# CAN.net
KiCad netlist of a schematic drawn in Altium Designer
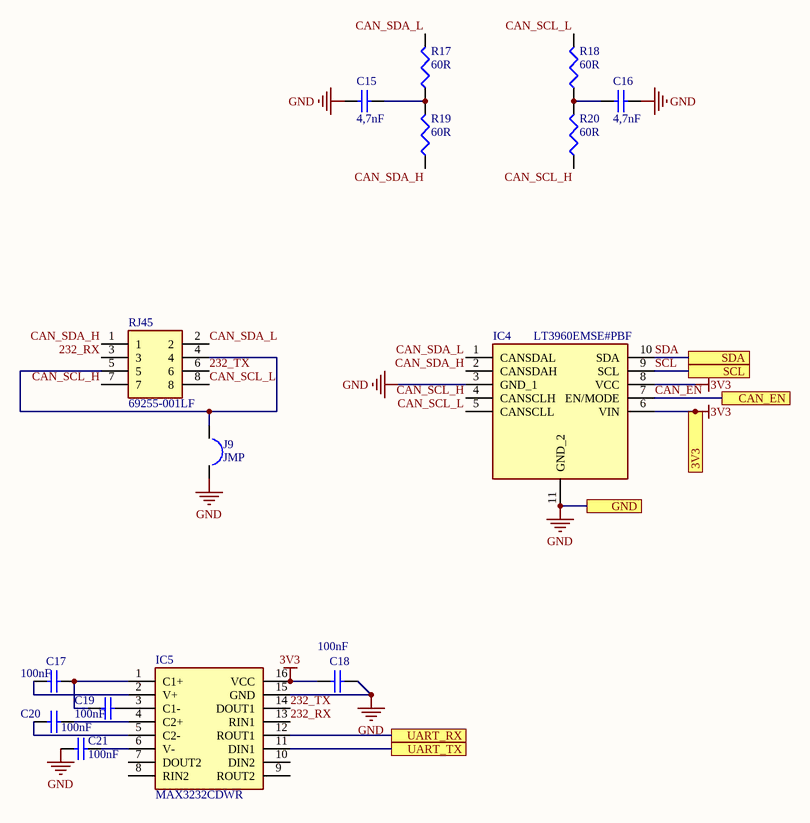
[diagram p0: CAN.SchDoc]

(export (version "E")
  (design (tool "Eeschema 10.0.6"))
  (components
    (comp (ref "C15")
      (value "4,7nF")
      (footprint "1608[0603]")
      (description "Capacitor (Semiconductor SIM Model)")
      (fields (field (name "PUBLISHER") "Altium Limited"))
      (libsource (lib "Miscellaneous Devices") (part "Cap Semi"))
    )
    (comp (ref "C16")
      (value "4,7nF")
      (footprint "1608[0603]")
      (description "Capacitor (Semiconductor SIM Model)")
      (fields (field (name "PUBLISHER") "Altium Limited"))
      (libsource (lib "Miscellaneous Devices") (part "Cap Semi"))
    )
    (comp (ref "C17")
      (value "100nF")
      (footprint "1608[0603]")
      (description "Capacitor (Semiconductor SIM Model)")
      (fields (field (name "PUBLISHER") "Altium Limited"))
      (libsource (lib "Miscellaneous Devices") (part "Cap Semi"))
    )
    (comp (ref "C18")
      (value "100nF")
      (footprint "1608[0603]")
      (description "Capacitor (Semiconductor SIM Model)")
      (fields (field (name "PUBLISHER") "Altium Limited"))
      (libsource (lib "Miscellaneous Devices") (part "Cap Semi"))
    )
    (comp (ref "C19")
      (value "100nF")
      (footprint "1608[0603]")
      (description "Capacitor (Semiconductor SIM Model)")
      (fields (field (name "PUBLISHER") "Altium Limited"))
      (libsource (lib "Miscellaneous Devices") (part "Cap Semi"))
    )
    (comp (ref "C20")
      (value "100nF")
      (footprint "1608[0603]")
      (description "Capacitor (Semiconductor SIM Model)")
      (fields (field (name "PUBLISHER") "Altium Limited"))
      (libsource (lib "Miscellaneous Devices") (part "Cap Semi"))
    )
    (comp (ref "C21")
      (value "100nF")
      (footprint "1608[0603]")
      (description "Capacitor (Semiconductor SIM Model)")
      (fields (field (name "PUBLISHER") "Altium Limited"))
      (libsource (lib "Miscellaneous Devices") (part "Cap Semi"))
    )
    (comp (ref "IC4")
      (value "LT3960EMSE#PBF")
      (footprint "SamacSys:SOP50P490X110-11N")
      (description "Integrated Circuit")
      (fields (field (name "MOUSER PART NUMBER") "584-LT3960EMSE#PBF"))
      (libsource (lib "*") (part "LT3960EMSE#PBF"))
    )
    (comp (ref "IC5")
      (value "MAX3232CDWR")
      (footprint "SOIC127P1030X265-16N")
      (description "Integrated Circuit")
      (fields (field (name "MOUSER PART NUMBER") "595-MAX3232CDWR"))
      (libsource (lib "*") (part "MAX3232CDWR"))
    )
    (comp (ref "J9") (value "JMP") (footprint "Jumper") (libsource (lib "SamacSys") (part "JMP")))
    (comp (ref "R17")
      (value "60R")
      (footprint "J1-0603")
      (description "Resistor")
      (fields (field (name "PUBLISHER") "Altium Limited"))
      (libsource (lib "Miscellaneous Devices") (part "Res3"))
    )
    (comp (ref "R18")
      (value "60R")
      (footprint "J1-0603")
      (description "Resistor")
      (fields (field (name "PUBLISHER") "Altium Limited"))
      (libsource (lib "Miscellaneous Devices") (part "Res3"))
    )
    (comp (ref "R19")
      (value "60R")
      (footprint "J1-0603")
      (description "Resistor")
      (fields (field (name "PUBLISHER") "Altium Limited"))
      (libsource (lib "Miscellaneous Devices") (part "Res3"))
    )
    (comp (ref "R20")
      (value "60R")
      (footprint "J1-0603")
      (description "Resistor")
      (fields (field (name "PUBLISHER") "Altium Limited"))
      (libsource (lib "Miscellaneous Devices") (part "Res3"))
    )
    (comp (ref "RJ45")
      (value "69255-001LF")
      (footprint "69255001LF")
      (description "Connector")
      (fields (field (name "MOUSER PART NUMBER") "649-69255-001LF"))
      (libsource (lib "*") (part "69255-001LF"))
    )
  )
  (nets
    (net (code "1") (name "/232_RX") (class "Default")
      (node (ref "IC5") (pin "13") (pinfunction "RIN1_13") (pintype "passive"))
      (node (ref "RJ45") (pin "3") (pinfunction "3_3") (pintype "passive"))
    )
    (net (code "2") (name "/232_TX") (class "Default")
      (node (ref "IC5") (pin "14") (pinfunction "DOUT1_14") (pintype "passive"))
      (node (ref "RJ45") (pin "6") (pinfunction "6_6") (pintype "passive"))
    )
    (net (code "3") (name "/CAN_EN") (class "Default")
      (node (ref "IC4") (pin "7") (pinfunction "EN/MODE_7") (pintype "passive"))
    )
    (net (code "4") (name "/CAN_SCL_H") (class "Default")
      (node (ref "IC4") (pin "4") (pinfunction "CANSCLH_4") (pintype "passive"))
      (node (ref "R20") (pin "1") (pinfunction "1_1") (pintype "passive"))
      (node (ref "RJ45") (pin "7") (pinfunction "7_7") (pintype "passive"))
    )
    (net (code "5") (name "/CAN_SCL_L") (class "Default")
      (node (ref "IC4") (pin "5") (pinfunction "CANSCLL_5") (pintype "passive"))
      (node (ref "R18") (pin "2") (pinfunction "2_2") (pintype "passive"))
      (node (ref "RJ45") (pin "8") (pinfunction "8_8") (pintype "passive"))
    )
    (net (code "6") (name "/CAN_SDA_H") (class "Default")
      (node (ref "IC4") (pin "2") (pinfunction "CANSDAH_2") (pintype "passive"))
      (node (ref "R19") (pin "1") (pinfunction "1_1") (pintype "passive"))
      (node (ref "RJ45") (pin "1") (pinfunction "1_1") (pintype "passive"))
    )
    (net (code "7") (name "/CAN_SDA_L") (class "Default")
      (node (ref "IC4") (pin "1") (pinfunction "CANSDAL_1") (pintype "passive"))
      (node (ref "R17") (pin "2") (pinfunction "2_2") (pintype "passive"))
      (node (ref "RJ45") (pin "2") (pinfunction "2_2") (pintype "passive"))
    )
    (net (code "8") (name "/SCL") (class "Default")
      (node (ref "IC4") (pin "9") (pinfunction "SCL_9") (pintype "passive"))
    )
    (net (code "9") (name "/SDA") (class "Default")
      (node (ref "IC4") (pin "10") (pinfunction "SDA_10") (pintype "passive"))
    )
    (net (code "10") (name "/UART_RX") (class "Default")
      (node (ref "IC5") (pin "12") (pinfunction "ROUT1_12") (pintype "passive"))
    )
    (net (code "11") (name "/UART_TX") (class "Default")
      (node (ref "IC5") (pin "11") (pinfunction "DIN1_11") (pintype "passive"))
    )
    (net (code "12") (name "3V3") (class "Default")
      (node (ref "C18") (pin "2") (pinfunction "2_2") (pintype "passive"))
      (node (ref "IC4") (pin "6") (pinfunction "VIN_6") (pintype "passive"))
      (node (ref "IC4") (pin "8") (pinfunction "VCC_8") (pintype "passive"))
      (node (ref "IC5") (pin "16") (pinfunction "VCC_16") (pintype "passive"))
    )
    (net (code "13") (name "GND") (class "Default")
      (node (ref "C15") (pin "1") (pinfunction "1_1") (pintype "passive"))
      (node (ref "C16") (pin "2") (pinfunction "2_2") (pintype "passive"))
      (node (ref "C18") (pin "1") (pinfunction "1_1") (pintype "passive"))
      (node (ref "C21") (pin "2") (pinfunction "2_2") (pintype "passive"))
      (node (ref "IC4") (pin "11") (pinfunction "GND_2_11") (pintype "passive"))
      (node (ref "IC4") (pin "3") (pinfunction "GND_1_3") (pintype "passive"))
      (node (ref "IC5") (pin "15") (pinfunction "GND_15") (pintype "passive"))
      (node (ref "J9") (pin "2") (pinfunction "2_2") (pintype "passive"))
    )
    (net (code "14") (name "Net-(C15-Pad2)") (class "Default")
      (node (ref "C15") (pin "2") (pinfunction "2_2") (pintype "passive"))
      (node (ref "R17") (pin "1") (pinfunction "1_1") (pintype "passive"))
      (node (ref "R19") (pin "2") (pinfunction "2_2") (pintype "passive"))
    )
    (net (code "15") (name "Net-(C16-Pad1)") (class "Default")
      (node (ref "C16") (pin "1") (pinfunction "1_1") (pintype "passive"))
      (node (ref "R18") (pin "1") (pinfunction "1_1") (pintype "passive"))
      (node (ref "R20") (pin "2") (pinfunction "2_2") (pintype "passive"))
    )
    (net (code "16") (name "Net-(IC5-C1+)") (class "Default")
      (node (ref "C17") (pin "2") (pinfunction "2_2") (pintype "passive"))
      (node (ref "C19") (pin "2") (pinfunction "2_2") (pintype "passive"))
      (node (ref "IC5") (pin "1") (pinfunction "C1+_1") (pintype "passive"))
    )
    (net (code "17") (name "Net-(IC5-C1-)") (class "Default")
      (node (ref "C19") (pin "1") (pinfunction "1_1") (pintype "passive"))
      (node (ref "IC5") (pin "3") (pinfunction "C1-_3") (pintype "passive"))
    )
    (net (code "18") (name "Net-(IC5-C2+)") (class "Default")
      (node (ref "C20") (pin "1") (pinfunction "1_1") (pintype "passive"))
      (node (ref "IC5") (pin "4") (pinfunction "C2+_4") (pintype "passive"))
    )
    (net (code "19") (name "Net-(IC5-C2-)") (class "Default")
      (node (ref "C20") (pin "2") (pinfunction "2_2") (pintype "passive"))
      (node (ref "IC5") (pin "5") (pinfunction "C2-_5") (pintype "passive"))
    )
    (net (code "20") (name "Net-(IC5-V+)") (class "Default")
      (node (ref "C17") (pin "1") (pinfunction "1_1") (pintype "passive"))
      (node (ref "IC5") (pin "2") (pinfunction "V+_2") (pintype "passive"))
    )
    (net (code "21") (name "Net-(IC5-V-)") (class "Default")
      (node (ref "C21") (pin "1") (pinfunction "1_1") (pintype "passive"))
      (node (ref "IC5") (pin "6") (pinfunction "V-_6") (pintype "passive"))
    )
    (net (code "22") (name "Net-(J9-Pad1)") (class "Default")
      (node (ref "J9") (pin "1") (pinfunction "1_1") (pintype "passive"))
      (node (ref "RJ45") (pin "4") (pinfunction "4_4") (pintype "passive"))
      (node (ref "RJ45") (pin "5") (pinfunction "5_5") (pintype "passive"))
    )
    (net (code "23") (name "unconnected-(IC5-DIN2-Pad10)") (class "Default")
      (node (ref "IC5") (pin "10") (pinfunction "DIN2_10") (pintype "passive"))
    )
    (net (code "24") (name "unconnected-(IC5-DOUT2-Pad7)") (class "Default")
      (node (ref "IC5") (pin "7") (pinfunction "DOUT2_7") (pintype "passive"))
    )
    (net (code "25") (name "unconnected-(IC5-RIN2-Pad8)") (class "Default")
      (node (ref "IC5") (pin "8") (pinfunction "RIN2_8") (pintype "passive"))
    )
    (net (code "26") (name "unconnected-(IC5-ROUT2-Pad9)") (class "Default")
      (node (ref "IC5") (pin "9") (pinfunction "ROUT2_9") (pintype "passive"))
    )
  )
)
